# pcbremote.net
KiCad netlist of a schematic drawn in EAGLE
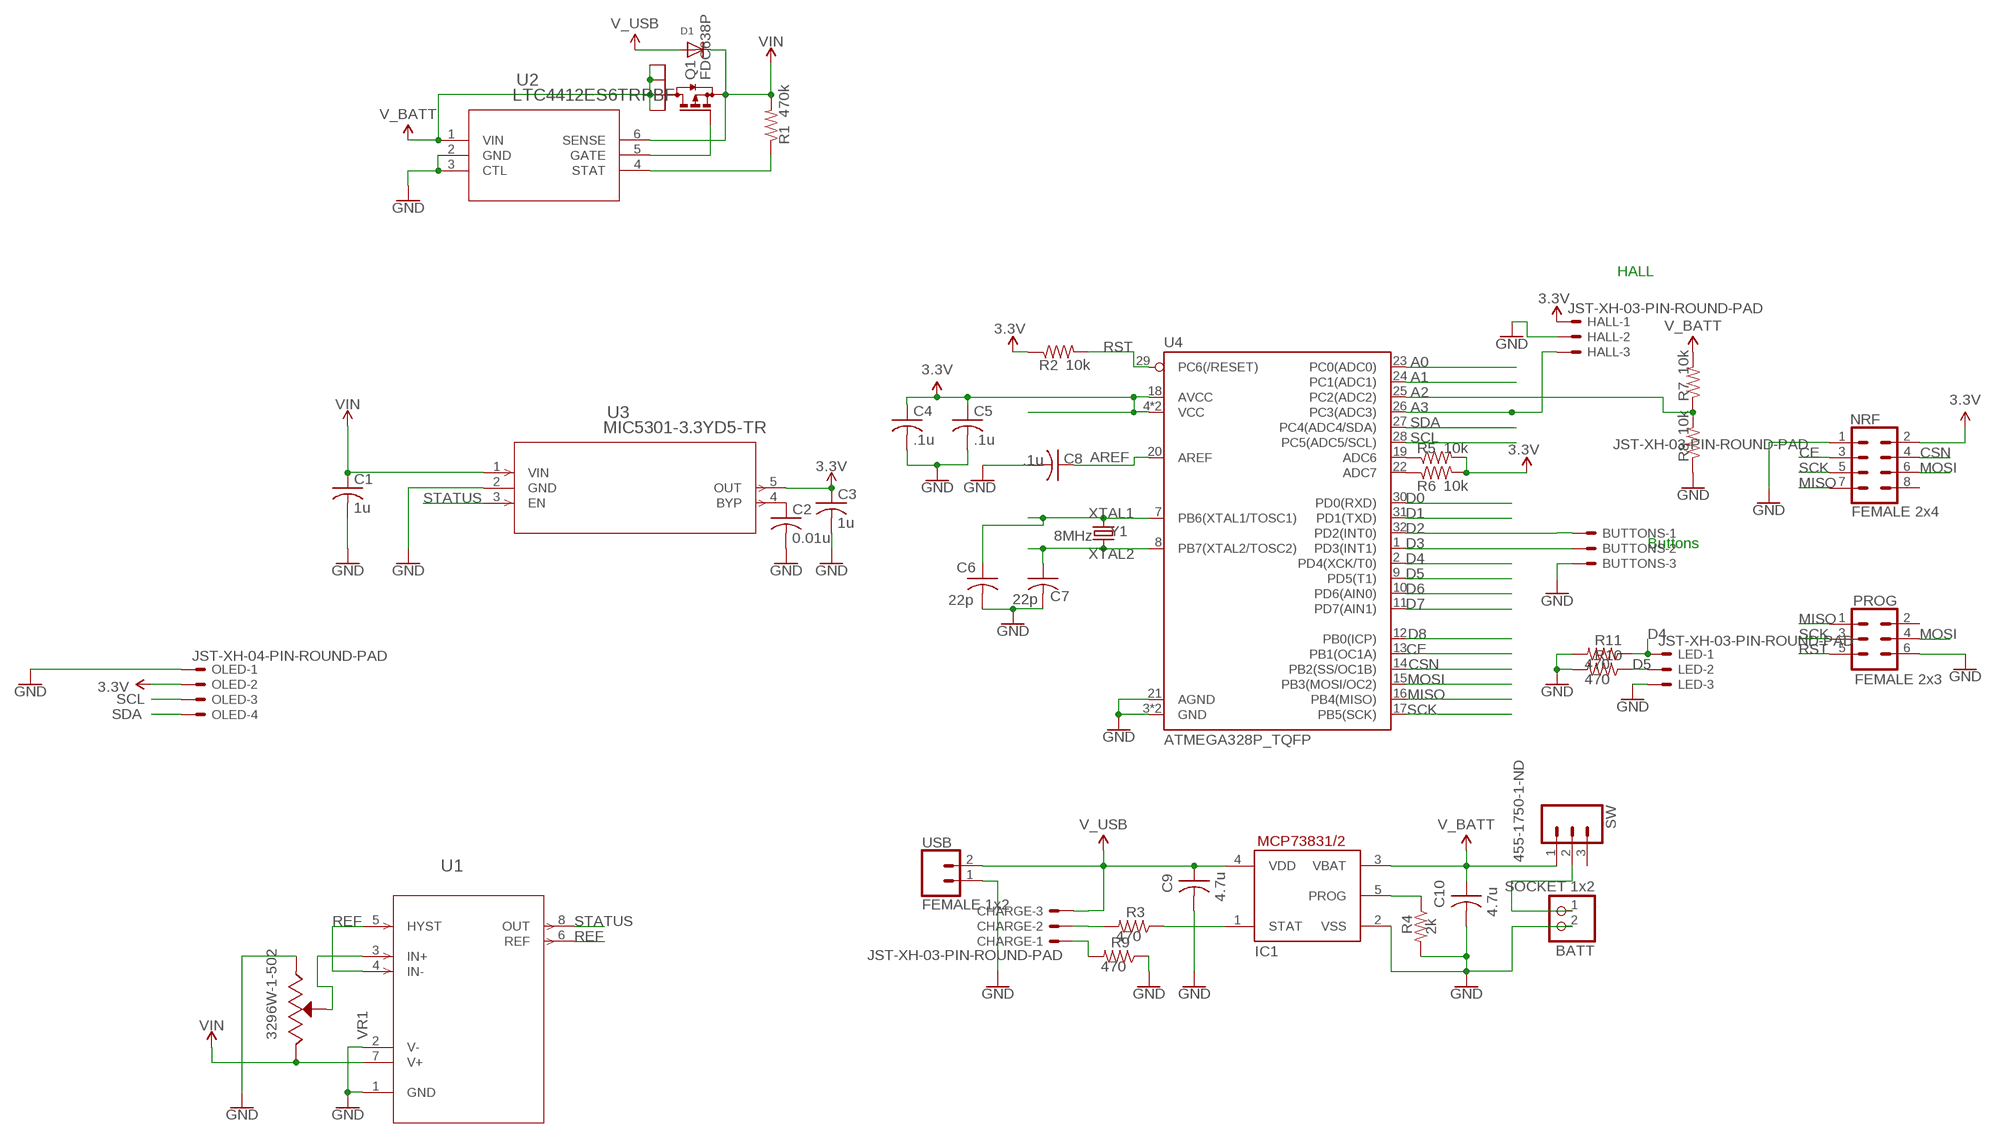
[diagram p0: schematic, sheet 1]

(export (version "E")
  (design (tool "Eeschema 10.0.6"))
  (components
    (comp (ref "BATT")
      (value "SOCKET 1x2")
      (footprint "eagle-import:JST-PH-2-THM")
      (libsource (lib "eagle-import") (part "JST_2PIN-THM"))
    )
    (comp (ref "BUTTONS")
      (value "JST-XH-03-PIN-ROUND-PAD")
      (footprint "eagle-import:JST-XH-03-PACKAGE-ROUND-PAD")
      (libsource (lib "eagle-import") (part "JST-XH-03-PIN-ROUND-PAD"))
    )
    (comp (ref "C1")
      (value "1u")
      (footprint "eagle-import:C0805")
      (libsource (lib "eagle-import") (part "C-USC0805"))
    )
    (comp (ref "C2")
      (value "0.01u")
      (footprint "eagle-import:C0805")
      (libsource (lib "eagle-import") (part "C-USC0805"))
    )
    (comp (ref "C3")
      (value "1u")
      (footprint "eagle-import:C0805")
      (libsource (lib "eagle-import") (part "C-USC0805"))
    )
    (comp (ref "C4")
      (value ".1u")
      (footprint "eagle-import:C0805")
      (libsource (lib "eagle-import") (part "C-USC0805"))
    )
    (comp (ref "C5")
      (value ".1u")
      (footprint "eagle-import:C0805")
      (libsource (lib "eagle-import") (part "C-USC0805"))
    )
    (comp (ref "C6")
      (value "22p")
      (footprint "eagle-import:C0805")
      (libsource (lib "eagle-import") (part "C-USC0805"))
    )
    (comp (ref "C7")
      (value "22p")
      (footprint "eagle-import:C0805")
      (libsource (lib "eagle-import") (part "C-USC0805"))
    )
    (comp (ref "C8")
      (value ".1u")
      (footprint "eagle-import:C0805")
      (libsource (lib "eagle-import") (part "C-USC0805"))
    )
    (comp (ref "C9")
      (value "4.7u")
      (footprint "eagle-import:C0805")
      (libsource (lib "eagle-import") (part "C-USC0805"))
    )
    (comp (ref "C10")
      (value "4.7u")
      (footprint "eagle-import:C0805")
      (libsource (lib "eagle-import") (part "C-USC0805"))
    )
    (comp (ref "CHARGE")
      (value "JST-XH-03-PIN-ROUND-PAD")
      (footprint "eagle-import:JST-XH-03-PACKAGE-ROUND-PAD")
      (libsource (lib "eagle-import") (part "JST-XH-03-PIN-ROUND-PAD"))
    )
    (comp (ref "D1")
      (value "DIODESOD-123")
      (footprint "eagle-import:SOD-123")
      (libsource (lib "eagle-import") (part "DIODESOD-123"))
    )
    (comp (ref "HALL")
      (value "JST-XH-03-PIN-ROUND-PAD")
      (footprint "eagle-import:JST-XH-03-PACKAGE-ROUND-PAD")
      (libsource (lib "eagle-import") (part "JST-XH-03-PIN-ROUND-PAD"))
    )
    (comp (ref "IC1")
      (value "MCP73831/OT")
      (footprint "eagle-import:SOT23-5L")
      (libsource (lib "eagle-import") (part "MCP73831/OT"))
    )
    (comp (ref "LED")
      (value "JST-XH-03-PIN-ROUND-PAD")
      (footprint "eagle-import:JST-XH-03-PACKAGE-ROUND-PAD")
      (libsource (lib "eagle-import") (part "JST-XH-03-PIN-ROUND-PAD"))
    )
    (comp (ref "NRF")
      (value "FEMALE 2x4")
      (footprint "eagle-import:2X4")
      (libsource (lib "eagle-import") (part "CONN_04X2"))
    )
    (comp (ref "OLED")
      (value "JST-XH-04-PIN-ROUND-PAD")
      (footprint "eagle-import:JST-XH-04-PACKAGE-ROUND-PAD")
      (libsource (lib "eagle-import") (part "JST-XH-04-PIN-ROUND-PAD"))
    )
    (comp (ref "PROG")
      (value "FEMALE 2x3")
      (footprint "eagle-import:2X3")
      (libsource (lib "eagle-import") (part "CONN_03X2FEMALE"))
    )
    (comp (ref "Q1")
      (value "FDC638P")
      (footprint "eagle-import:SSOT-6")
      (fields (field (name "DIGI-KEY_PART_NUMBER") "FDC638PCT-ND") (field (name "MF") "ON Semiconductor"))
      (libsource (lib "eagle-import") (part "FDC638P"))
    )
    (comp (ref "R1")
      (value "470k")
      (footprint "eagle-import:R0805")
      (libsource (lib "eagle-import") (part "R-US_R0805"))
    )
    (comp (ref "R2")
      (value "10k")
      (footprint "eagle-import:R0805")
      (libsource (lib "eagle-import") (part "R-US_R0805"))
    )
    (comp (ref "R3")
      (value "470")
      (footprint "eagle-import:R0805")
      (libsource (lib "eagle-import") (part "R-US_R0805"))
    )
    (comp (ref "R4")
      (value "2k")
      (footprint "eagle-import:R0805")
      (libsource (lib "eagle-import") (part "R-US_R0805"))
    )
    (comp (ref "R5")
      (value "10k")
      (footprint "eagle-import:R0805")
      (libsource (lib "eagle-import") (part "R-US_R0805"))
    )
    (comp (ref "R6")
      (value "10k")
      (footprint "eagle-import:R0805")
      (libsource (lib "eagle-import") (part "R-US_R0805"))
    )
    (comp (ref "R7")
      (value "10k")
      (footprint "eagle-import:R0805")
      (libsource (lib "eagle-import") (part "R-US_R0805"))
    )
    (comp (ref "R8")
      (value "10k")
      (footprint "eagle-import:R0805")
      (libsource (lib "eagle-import") (part "R-US_R0805"))
    )
    (comp (ref "R9")
      (value "470")
      (footprint "eagle-import:R0805")
      (libsource (lib "eagle-import") (part "R-US_R0805"))
    )
    (comp (ref "R10")
      (value "470")
      (footprint "eagle-import:R0805")
      (libsource (lib "eagle-import") (part "R-US_R0805"))
    )
    (comp (ref "R11")
      (value "470")
      (footprint "eagle-import:R0805")
      (libsource (lib "eagle-import") (part "R-US_R0805"))
    )
    (comp (ref "SW")
      (value "455-1750-1-ND")
      (footprint "eagle-import:1X03")
      (libsource (lib "eagle-import") (part "CONN_03"))
    )
    (comp (ref "U1")
      (value "LTC1540CS8PBF")
      (footprint "eagle-import:SO-8_S_LIT")
      (fields (field (name "MANUFACTURER_PART_NUMBER") "ltc1540cs8#pbf"))
      (libsource (lib "eagle-import") (part "LTC1540CS8PBF"))
    )
    (comp (ref "U2")
      (value "LTC4412ES6TRPBF")
      (footprint "eagle-import:TSOT-23_S6_LIT")
      (fields (field (name "MANUFACTURER_PART_NUMBER") "LTC4412ES6#TRPBF"))
      (libsource (lib "eagle-import") (part "LTC4412ES6TRPBF"))
    )
    (comp (ref "U3")
      (value "MIC5301-3.3YD5-TR")
      (footprint "eagle-import:TSOT-23-5_D5_MCH")
      (fields (field (name "COPYRIGHT") "Copyright (C) 2018 Accelerated Designs. All rights reserved"))
      (libsource (lib "eagle-import") (part "MIC5301-3.3YD5-TR"))
    )
    (comp (ref "U4")
      (value "ATMEGA328P_TQFP")
      (footprint "eagle-import:TQFP32-08")
      (libsource (lib "eagle-import") (part "ATMEGA328P_TQFP"))
    )
    (comp (ref "USB")
      (value "FEMALE 1x2")
      (footprint "eagle-import:1X02")
      (libsource (lib "eagle-import") (part "CONN_02"))
    )
    (comp (ref "VR1")
      (value "3296W-1-502")
      (footprint "eagle-import:TRIM_3296W-1-502")
      (fields (field (name "DIGI-KEY_PART_NUMBER") "3296W-502LF-ND") (field (name "MF") "Bourns"))
      (libsource (lib "eagle-import") (part "3296W-1-502"))
    )
    (comp (ref "Y1")
      (value "8MHz")
      (footprint "eagle-import:CRYSTAL-SMD-5X3.2-4PAD")
      (libsource (lib "eagle-import") (part "CRYSTAL-8MHZSMD-5X3.2"))
    )
  )
  (nets
    (net (code "1") (name "/A0") (class "Default")
      (node (ref "U4") (pin "23") (pinfunction "PC0(ADC0)_23") (pintype "bidirectional"))
    )
    (net (code "2") (name "/A1") (class "Default")
      (node (ref "U4") (pin "24") (pinfunction "PC1(ADC1)_24") (pintype "bidirectional"))
    )
    (net (code "3") (name "/A2") (class "Default")
      (node (ref "R7") (pin "1") (pinfunction "1_1") (pintype "passive"))
      (node (ref "R8") (pin "2") (pinfunction "2_2") (pintype "passive"))
      (node (ref "U4") (pin "25") (pinfunction "PC2(ADC2)_25") (pintype "bidirectional"))
    )
    (net (code "4") (name "/A3") (class "Default")
      (node (ref "HALL") (pin "3") (pinfunction "S_3") (pintype "passive"))
      (node (ref "U4") (pin "26") (pinfunction "PC3(ADC3)_26") (pintype "bidirectional"))
    )
    (net (code "5") (name "/AREF") (class "Default")
      (node (ref "C8") (pin "1") (pinfunction "1_1") (pintype "passive"))
      (node (ref "U4") (pin "20") (pinfunction "AREF_20") (pintype "bidirectional"))
    )
    (net (code "6") (name "/CE") (class "Default")
      (node (ref "NRF") (pin "3") (pinfunction "3_3") (pintype "passive"))
      (node (ref "U4") (pin "13") (pinfunction "PB1(OC1A)_13") (pintype "bidirectional"))
    )
    (net (code "7") (name "/CSN") (class "Default")
      (node (ref "NRF") (pin "4") (pinfunction "4_4") (pintype "passive"))
      (node (ref "U4") (pin "14") (pinfunction "PB2(SS/OC1B)_14") (pintype "bidirectional"))
    )
    (net (code "8") (name "/D0") (class "Default")
      (node (ref "U4") (pin "30") (pinfunction "PD0(RXD)_30") (pintype "bidirectional"))
    )
    (net (code "9") (name "/D1") (class "Default")
      (node (ref "U4") (pin "31") (pinfunction "PD1(TXD)_31") (pintype "bidirectional"))
    )
    (net (code "10") (name "/D2") (class "Default")
      (node (ref "BUTTONS") (pin "1") (pinfunction "S_1") (pintype "passive"))
      (node (ref "U4") (pin "32") (pinfunction "PD2(INT0)_32") (pintype "bidirectional"))
    )
    (net (code "11") (name "/D3") (class "Default")
      (node (ref "BUTTONS") (pin "2") (pinfunction "S_2") (pintype "passive"))
      (node (ref "U4") (pin "1") (pinfunction "PD3(INT1)_1") (pintype "bidirectional"))
    )
    (net (code "12") (name "/D4") (class "Default")
      (node (ref "LED") (pin "1") (pinfunction "S_1") (pintype "passive"))
      (node (ref "R11") (pin "1") (pinfunction "1_1") (pintype "passive"))
      (node (ref "U4") (pin "2") (pinfunction "PD4(XCK/T0)_2") (pintype "bidirectional"))
    )
    (net (code "13") (name "/D5") (class "Default")
      (node (ref "LED") (pin "2") (pinfunction "S_2") (pintype "passive"))
      (node (ref "R10") (pin "1") (pinfunction "1_1") (pintype "passive"))
      (node (ref "U4") (pin "9") (pinfunction "PD5(T1)_9") (pintype "bidirectional"))
    )
    (net (code "14") (name "/D6") (class "Default")
      (node (ref "U4") (pin "10") (pinfunction "PD6(AIN0)_10") (pintype "bidirectional"))
    )
    (net (code "15") (name "/D7") (class "Default")
      (node (ref "U4") (pin "11") (pinfunction "PD7(AIN1)_11") (pintype "bidirectional"))
    )
    (net (code "16") (name "/D8") (class "Default")
      (node (ref "U4") (pin "12") (pinfunction "PB0(ICP)_12") (pintype "bidirectional"))
    )
    (net (code "17") (name "/MISO") (class "Default")
      (node (ref "NRF") (pin "7") (pinfunction "7_7") (pintype "passive"))
      (node (ref "PROG") (pin "1") (pinfunction "1_1") (pintype "bidirectional"))
      (node (ref "U4") (pin "16") (pinfunction "PB4(MISO)_16") (pintype "bidirectional"))
    )
    (net (code "18") (name "/MOSI") (class "Default")
      (node (ref "NRF") (pin "6") (pinfunction "6_6") (pintype "passive"))
      (node (ref "PROG") (pin "4") (pinfunction "4_4") (pintype "bidirectional"))
      (node (ref "U4") (pin "15") (pinfunction "PB3(MOSI/OC2)_15") (pintype "bidirectional"))
    )
    (net (code "19") (name "/REF") (class "Default")
      (node (ref "U1") (pin "4") (pinfunction "IN-_4") (pintype "input"))
      (node (ref "U1") (pin "5") (pinfunction "HYST_5") (pintype "input"))
      (node (ref "U1") (pin "6") (pinfunction "REF_6") (pintype "output"))
    )
    (net (code "20") (name "/RST") (class "Default")
      (node (ref "PROG") (pin "5") (pinfunction "5_5") (pintype "bidirectional"))
      (node (ref "R2") (pin "2") (pinfunction "2_2") (pintype "passive"))
      (node (ref "U4") (pin "29") (pinfunction "PC6(/RESET)_29") (pintype "bidirectional"))
    )
    (net (code "21") (name "/SCK") (class "Default")
      (node (ref "NRF") (pin "5") (pinfunction "5_5") (pintype "passive"))
      (node (ref "PROG") (pin "3") (pinfunction "3_3") (pintype "bidirectional"))
      (node (ref "U4") (pin "17") (pinfunction "PB5(SCK)_17") (pintype "bidirectional"))
    )
    (net (code "22") (name "/SCL") (class "Default")
      (node (ref "OLED") (pin "3") (pinfunction "S_3") (pintype "passive"))
      (node (ref "U4") (pin "28") (pinfunction "PC5(ADC5/SCL)_28") (pintype "bidirectional"))
    )
    (net (code "23") (name "/SDA") (class "Default")
      (node (ref "OLED") (pin "4") (pinfunction "S_4") (pintype "passive"))
      (node (ref "U4") (pin "27") (pinfunction "PC4(ADC4/SDA)_27") (pintype "bidirectional"))
    )
    (net (code "24") (name "/STATUS") (class "Default")
      (node (ref "U1") (pin "8") (pinfunction "OUT_8") (pintype "output"))
      (node (ref "U3") (pin "3") (pinfunction "EN_3") (pintype "input"))
    )
    (net (code "25") (name "/XTAL1") (class "Default")
      (node (ref "C6") (pin "1") (pinfunction "1_1") (pintype "passive"))
      (node (ref "U4") (pin "7") (pinfunction "PB6(XTAL1/TOSC1)_7") (pintype "bidirectional"))
      (node (ref "Y1") (pin "1") (pinfunction "1_1") (pintype "passive"))
    )
    (net (code "26") (name "/XTAL2") (class "Default")
      (node (ref "C7") (pin "1") (pinfunction "1_1") (pintype "passive"))
      (node (ref "U4") (pin "8") (pinfunction "PB7(XTAL2/TOSC2)_8") (pintype "bidirectional"))
      (node (ref "Y1") (pin "3") (pinfunction "2_3") (pintype "passive"))
    )
    (net (code "27") (name "3.3V") (class "Default")
      (node (ref "C3") (pin "1") (pinfunction "1_1") (pintype "passive"))
      (node (ref "C4") (pin "1") (pinfunction "1_1") (pintype "passive"))
      (node (ref "C5") (pin "1") (pinfunction "1_1") (pintype "passive"))
      (node (ref "HALL") (pin "1") (pinfunction "S_1") (pintype "passive"))
      (node (ref "NRF") (pin "2") (pinfunction "2_2") (pintype "passive"))
      (node (ref "OLED") (pin "2") (pinfunction "S_2") (pintype "passive"))
      (node (ref "R2") (pin "1") (pinfunction "1_1") (pintype "passive"))
      (node (ref "R5") (pin "2") (pinfunction "2_2") (pintype "passive"))
      (node (ref "R6") (pin "2") (pinfunction "2_2") (pintype "passive"))
      (node (ref "U3") (pin "5") (pinfunction "OUT_5") (pintype "output"))
      (node (ref "U4") (pin "18") (pinfunction "AVCC_18") (pintype "bidirectional"))
      (node (ref "U4") (pin "4") (pinfunction "VCC_4") (pintype "bidirectional"))
      (node (ref "U4") (pin "6") (pinfunction "VCC_6") (pintype "bidirectional"))
    )
    (net (code "28") (name "GND") (class "Default")
      (node (ref "BATT") (pin "2") (pinfunction "1_2") (pintype "passive"))
      (node (ref "BUTTONS") (pin "3") (pinfunction "S_3") (pintype "passive"))
      (node (ref "C1") (pin "2") (pinfunction "2_2") (pintype "passive"))
      (node (ref "C10") (pin "2") (pinfunction "2_2") (pintype "passive"))
      (node (ref "C2") (pin "2") (pinfunction "2_2") (pintype "passive"))
      (node (ref "C3") (pin "2") (pinfunction "2_2") (pintype "passive"))
      (node (ref "C4") (pin "2") (pinfunction "2_2") (pintype "passive"))
      (node (ref "C5") (pin "2") (pinfunction "2_2") (pintype "passive"))
      (node (ref "C6") (pin "2") (pinfunction "2_2") (pintype "passive"))
      (node (ref "C7") (pin "2") (pinfunction "2_2") (pintype "passive"))
      (node (ref "C8") (pin "2") (pinfunction "2_2") (pintype "passive"))
      (node (ref "C9") (pin "2") (pinfunction "2_2") (pintype "passive"))
      (node (ref "HALL") (pin "2") (pinfunction "S_2") (pintype "passive"))
      (node (ref "IC1") (pin "2") (pinfunction "VSS_2") (pintype "power_in"))
      (node (ref "LED") (pin "3") (pinfunction "S_3") (pintype "passive"))
      (node (ref "NRF") (pin "1") (pinfunction "1_1") (pintype "passive"))
      (node (ref "OLED") (pin "1") (pinfunction "S_1") (pintype "passive"))
      (node (ref "PROG") (pin "6") (pinfunction "6_6") (pintype "bidirectional"))
      (node (ref "R10") (pin "2") (pinfunction "2_2") (pintype "passive"))
      (node (ref "R11") (pin "2") (pinfunction "2_2") (pintype "passive"))
      (node (ref "R4") (pin "2") (pinfunction "2_2") (pintype "passive"))
      (node (ref "R8") (pin "1") (pinfunction "1_1") (pintype "passive"))
      (node (ref "R9") (pin "1") (pinfunction "1_1") (pintype "passive"))
      (node (ref "U1") (pin "1") (pinfunction "GND_1") (pintype "power_in"))
      (node (ref "U1") (pin "2") (pinfunction "V-_2") (pintype "power_in"))
      (node (ref "U2") (pin "2") (pinfunction "GND_2") (pintype "power_in"))
      (node (ref "U2") (pin "3") (pinfunction "CTL_3") (pintype "input"))
      (node (ref "U3") (pin "2") (pinfunction "GND_2") (pintype "power_in"))
      (node (ref "U4") (pin "21") (pinfunction "AGND_21") (pintype "bidirectional"))
      (node (ref "U4") (pin "3") (pinfunction "GND_3") (pintype "bidirectional"))
      (node (ref "U4") (pin "5") (pinfunction "GND_5") (pintype "bidirectional"))
      (node (ref "USB") (pin "1") (pinfunction "1_1") (pintype "passive"))
      (node (ref "VR1") (pin "3") (pinfunction "CW_3") (pintype "passive"))
    )
    (net (code "29") (name "Net-(BATT-2)") (class "Default")
      (node (ref "BATT") (pin "1") (pinfunction "2_1") (pintype "passive"))
      (node (ref "SW") (pin "2") (pinfunction "2_2") (pintype "passive"))
    )
    (net (code "30") (name "Net-(CHARGEA-S)") (class "Default")
      (node (ref "CHARGE") (pin "1") (pinfunction "S_1") (pintype "passive"))
      (node (ref "R9") (pin "2") (pinfunction "2_2") (pintype "passive"))
    )
    (net (code "31") (name "Net-(CHARGEB-S)") (class "Default")
      (node (ref "CHARGE") (pin "2") (pinfunction "S_2") (pintype "passive"))
      (node (ref "R3") (pin "2") (pinfunction "2_2") (pintype "passive"))
    )
    (net (code "32") (name "Net-(IC1-PROG)") (class "Default")
      (node (ref "IC1") (pin "5") (pinfunction "PROG_5") (pintype "input"))
      (node (ref "R4") (pin "1") (pinfunction "1_1") (pintype "passive"))
    )
    (net (code "33") (name "Net-(IC1-STAT)") (class "Default")
      (node (ref "IC1") (pin "1") (pinfunction "STAT_1") (pintype "output"))
      (node (ref "R3") (pin "1") (pinfunction "1_1") (pintype "passive"))
    )
    (net (code "34") (name "Net-(Q1-G)") (class "Default")
      (node (ref "Q1") (pin "3") (pinfunction "G_3") (pintype "passive"))
      (node (ref "U2") (pin "5") (pinfunction "GATE_5") (pintype "passive"))
    )
    (net (code "35") (name "Net-(U1-IN+)") (class "Default")
      (node (ref "U1") (pin "3") (pinfunction "IN+_3") (pintype "input"))
      (node (ref "VR1") (pin "2") (pinfunction "WIPER_2") (pintype "passive"))
    )
    (net (code "36") (name "Net-(U2-STAT)") (class "Default")
      (node (ref "R1") (pin "1") (pinfunction "1_1") (pintype "passive"))
      (node (ref "U2") (pin "4") (pinfunction "STAT_4") (pintype "output"))
    )
    (net (code "37") (name "Net-(U3-BYP)") (class "Default")
      (node (ref "C2") (pin "1") (pinfunction "1_1") (pintype "passive"))
      (node (ref "U3") (pin "4") (pinfunction "BYP_4") (pintype "output"))
    )
    (net (code "38") (name "Net-(U4-ADC6)") (class "Default")
      (node (ref "R5") (pin "1") (pinfunction "1_1") (pintype "passive"))
      (node (ref "U4") (pin "19") (pinfunction "ADC6_19") (pintype "bidirectional"))
    )
    (net (code "39") (name "Net-(U4-ADC7)") (class "Default")
      (node (ref "R6") (pin "1") (pinfunction "1_1") (pintype "passive"))
      (node (ref "U4") (pin "22") (pinfunction "ADC7_22") (pintype "bidirectional"))
    )
    (net (code "40") (name "VIN") (class "Default")
      (node (ref "C1") (pin "1") (pinfunction "1_1") (pintype "passive"))
      (node (ref "D1") (pin "C") (pinfunction "C_C") (pintype "passive"))
      (node (ref "Q1") (pin "4") (pinfunction "S_4") (pintype "passive"))
      (node (ref "R1") (pin "2") (pinfunction "2_2") (pintype "passive"))
      (node (ref "U1") (pin "7") (pinfunction "V+_7") (pintype "power_in"))
      (node (ref "U2") (pin "6") (pinfunction "SENSE_6") (pintype "input"))
      (node (ref "U3") (pin "1") (pinfunction "VIN_1") (pintype "input"))
      (node (ref "VR1") (pin "1") (pinfunction "CCW_1") (pintype "passive"))
    )
    (net (code "41") (name "V_BATT") (class "Default")
      (node (ref "C10") (pin "1") (pinfunction "1_1") (pintype "passive"))
      (node (ref "IC1") (pin "3") (pinfunction "VBAT_3") (pintype "bidirectional"))
      (node (ref "Q1") (pin "1") (pinfunction "D4_1") (pintype "passive"))
      (node (ref "Q1") (pin "2") (pinfunction "D1_2") (pintype "passive"))
      (node (ref "Q1") (pin "5") (pinfunction "D2_5") (pintype "passive"))
      (node (ref "Q1") (pin "6") (pinfunction "D3_6") (pintype "passive"))
      (node (ref "R7") (pin "2") (pinfunction "2_2") (pintype "passive"))
      (node (ref "SW") (pin "1") (pinfunction "1_1") (pintype "passive"))
      (node (ref "U2") (pin "1") (pinfunction "VIN_1") (pintype "input"))
    )
    (net (code "42") (name "V_USB") (class "Default")
      (node (ref "C9") (pin "1") (pinfunction "1_1") (pintype "passive"))
      (node (ref "CHARGE") (pin "3") (pinfunction "S_3") (pintype "passive"))
      (node (ref "D1") (pin "A") (pinfunction "A_A") (pintype "passive"))
      (node (ref "IC1") (pin "4") (pinfunction "VDD_4") (pintype "power_in"))
      (node (ref "USB") (pin "2") (pinfunction "2_2") (pintype "passive"))
    )
    (net (code "43") (name "unconnected-(NRF-Pad8)") (class "Default")
      (node (ref "NRF") (pin "8") (pinfunction "8_8") (pintype "passive"))
    )
    (net (code "44") (name "unconnected-(PROG-Pad2)") (class "Default")
      (node (ref "PROG") (pin "2") (pinfunction "2_2") (pintype "bidirectional"))
    )
    (net (code "45") (name "unconnected-(SW-Pad3)") (class "Default")
      (node (ref "SW") (pin "3") (pinfunction "3_3") (pintype "passive"))
    )
  )
)
